# DataLogger_ver1.net
KiCad netlist of a schematic drawn in EAGLE
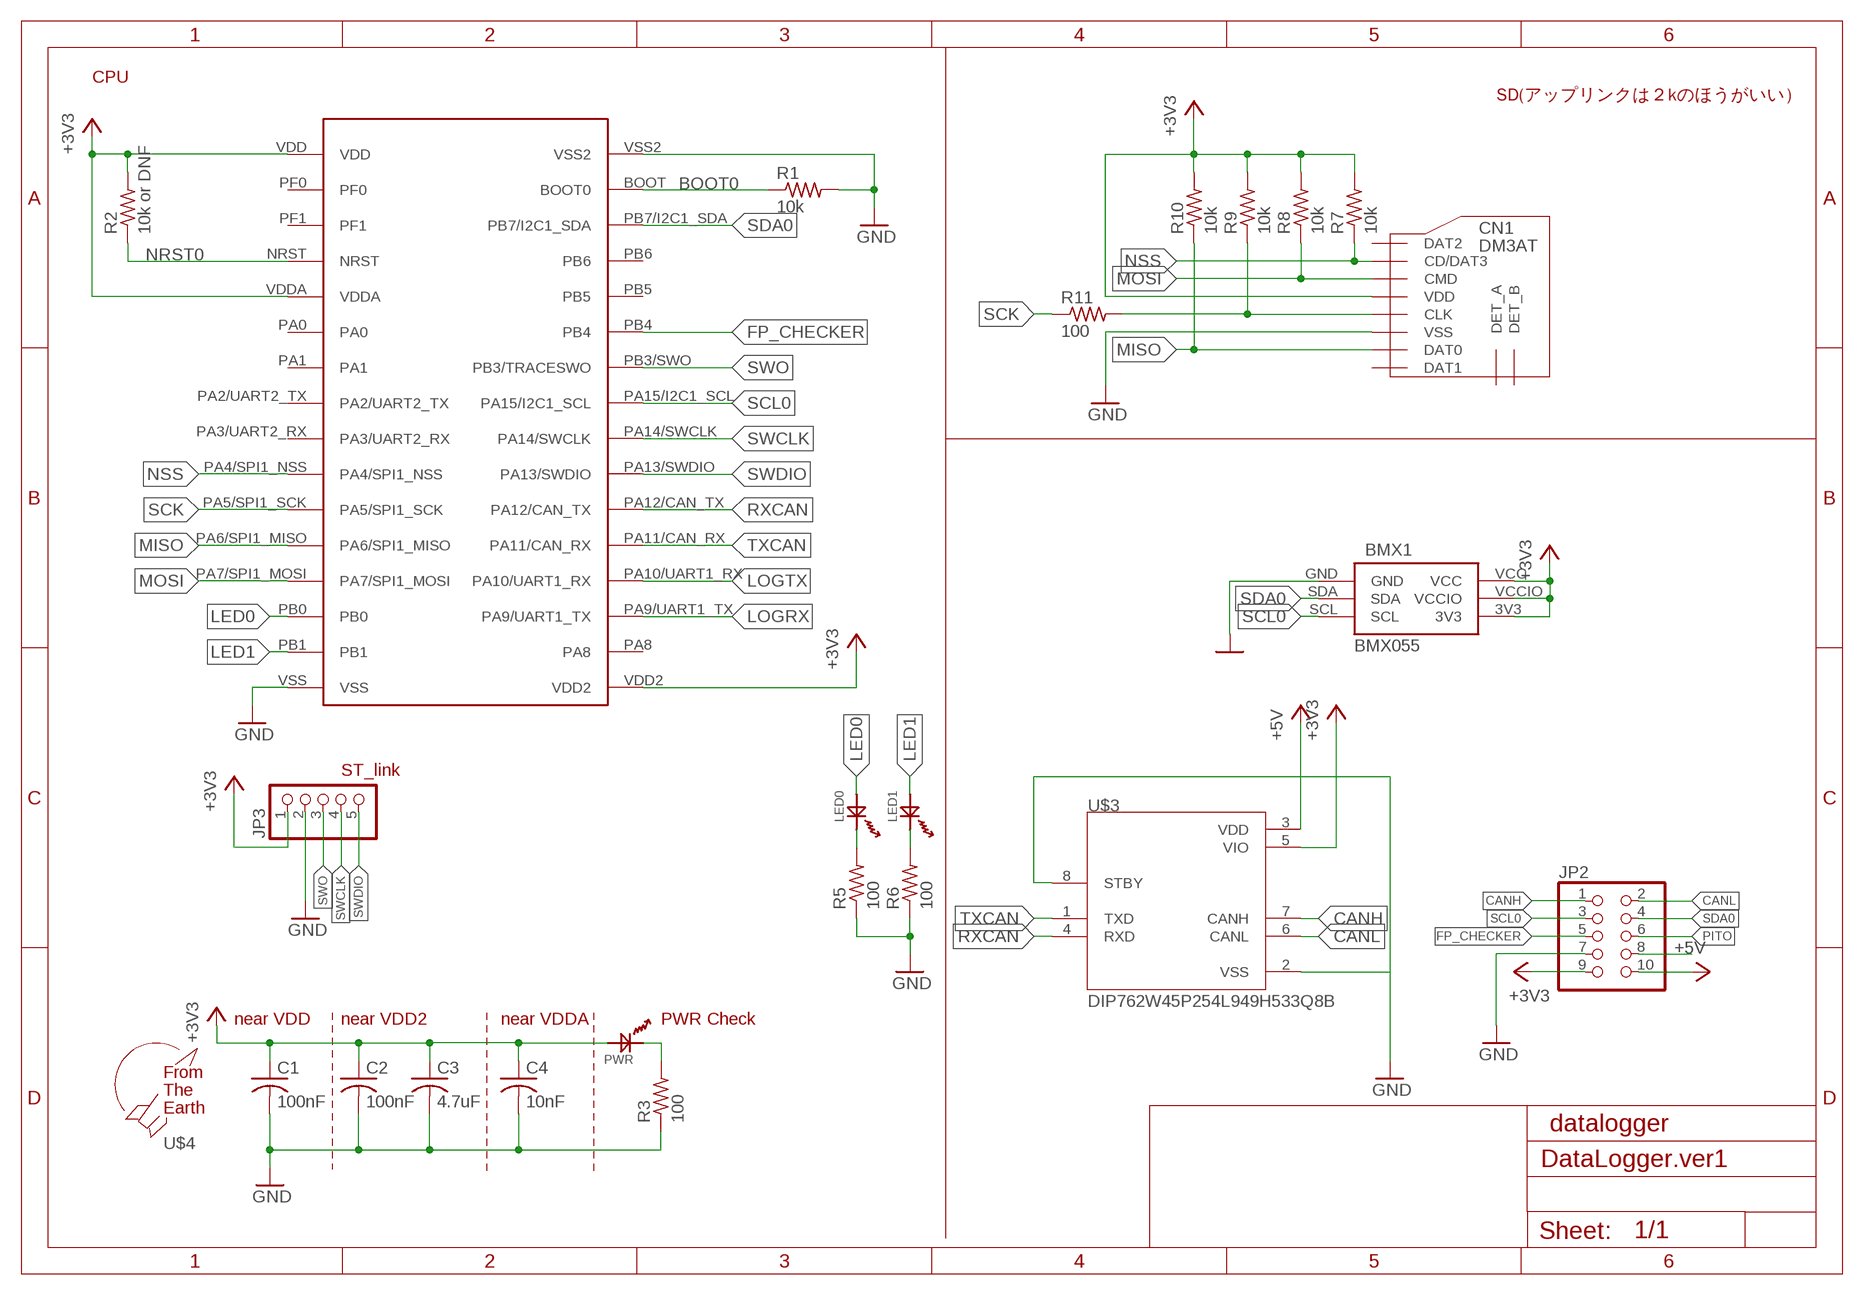
[diagram p0: schematic, sheet 1]

(export (version "E")
  (design (tool "Eeschema 10.0.6"))
  (components
    (comp (ref "BMX1")
      (value "BMX055")
      (footprint "eagle-import:BMX055")
      (libsource (lib "eagle-import") (part "BMX055"))
    )
    (comp (ref "C1")
      (value "100nF")
      (footprint "eagle-import:C1608")
      (libsource (lib "eagle-import") (part "C-USC1608"))
    )
    (comp (ref "C2")
      (value "100nF")
      (footprint "eagle-import:C1608")
      (libsource (lib "eagle-import") (part "C-USC1608"))
    )
    (comp (ref "C3")
      (value "4.7uF")
      (footprint "eagle-import:C1608")
      (libsource (lib "eagle-import") (part "C-USC1608"))
    )
    (comp (ref "C4")
      (value "10nF")
      (footprint "eagle-import:C1608")
      (libsource (lib "eagle-import") (part "C-USC1608"))
    )
    (comp (ref "CN1")
      (value "DM3AT")
      (footprint "eagle-import:DM3AT")
      (libsource (lib "eagle-import") (part "DM3AT"))
    )
    (comp (ref "JP2")
      (value "PINHD-2X5/90")
      (footprint "eagle-import:2X05_90")
      (libsource (lib "eagle-import") (part "PINHD-2X5/90"))
    )
    (comp (ref "JP3")
      (value "PINHD-1X5/90")
      (footprint "eagle-import:1X05_90")
      (libsource (lib "eagle-import") (part "PINHD-1X5/90"))
    )
    (comp (ref "LED0")
      (value "OSXX1608C1A")
      (footprint "eagle-import:OSXX1608C1A")
      (libsource (lib "eagle-import") (part "OSXX1608C1A"))
    )
    (comp (ref "LED1")
      (value "OSXX1608C1A")
      (footprint "eagle-import:OSXX1608C1A")
      (libsource (lib "eagle-import") (part "OSXX1608C1A"))
    )
    (comp (ref "PWR")
      (value "OSXX1608C1A")
      (footprint "eagle-import:OSXX1608C1A")
      (libsource (lib "eagle-import") (part "OSXX1608C1A"))
    )
    (comp (ref "R1")
      (value "10k")
      (footprint "eagle-import:R0603")
      (libsource (lib "eagle-import") (part "R-US_R0603"))
    )
    (comp (ref "R2")
      (value "10k or DNF")
      (footprint "eagle-import:R0603")
      (libsource (lib "eagle-import") (part "R-US_R0603"))
    )
    (comp (ref "R3")
      (value "100")
      (footprint "eagle-import:R0603")
      (libsource (lib "eagle-import") (part "R-US_R0603"))
    )
    (comp (ref "R5")
      (value "100")
      (footprint "eagle-import:R0603")
      (libsource (lib "eagle-import") (part "R-US_R0603"))
    )
    (comp (ref "R6")
      (value "100")
      (footprint "eagle-import:R0603")
      (libsource (lib "eagle-import") (part "R-US_R0603"))
    )
    (comp (ref "R7")
      (value "10k")
      (footprint "eagle-import:R0603")
      (libsource (lib "eagle-import") (part "R-US_R0603"))
    )
    (comp (ref "R8")
      (value "10k")
      (footprint "eagle-import:R0603")
      (libsource (lib "eagle-import") (part "R-US_R0603"))
    )
    (comp (ref "R9")
      (value "10k")
      (footprint "eagle-import:R0603")
      (libsource (lib "eagle-import") (part "R-US_R0603"))
    )
    (comp (ref "R10")
      (value "10k")
      (footprint "eagle-import:R0603")
      (libsource (lib "eagle-import") (part "R-US_R0603"))
    )
    (comp (ref "R11")
      (value "100")
      (footprint "eagle-import:R0603")
      (libsource (lib "eagle-import") (part "R-US_R0603"))
    )
    (comp (ref "STM0")
      (value "STM32F303K8")
      (footprint "eagle-import:STM32F303K8")
      (libsource (lib "eagle-import") (part "STM32F303K8"))
    )
    (comp (ref "U$3")
      (value "DIP762W45P254L949H533Q8B")
      (footprint "eagle-import:DIP762W45P254L949H533Q8B")
      (libsource (lib "eagle-import") (part "DIP762W45P254L949H533Q8B"))
    )
    (comp (ref "U$4")
      (value "F.T.E.LOGO")
      (footprint "eagle-import:LOGO")
      (libsource (lib "eagle-import") (part "F.T.E.LOGO"))
    )
  )
  (nets
    (net (code "1") (name "+3V3") (class "Default")
      (node (ref "BMX1") (pin "3V3") (pinfunction "3V3_3V3") (pintype "power_in"))
      (node (ref "BMX1") (pin "VCC") (pinfunction "VCC_VCC") (pintype "power_in"))
      (node (ref "BMX1") (pin "VCCIO") (pinfunction "VCCIO_VCCIO") (pintype "power_in"))
      (node (ref "C1") (pin "1") (pinfunction "1_1") (pintype "passive"))
      (node (ref "C2") (pin "1") (pinfunction "1_1") (pintype "passive"))
      (node (ref "C3") (pin "1") (pinfunction "1_1") (pintype "passive"))
      (node (ref "C4") (pin "1") (pinfunction "1_1") (pintype "passive"))
      (node (ref "CN1") (pin "VDD") (pinfunction "VDD_VDD") (pintype "bidirectional"))
      (node (ref "JP2") (pin "9") (pinfunction "9_9") (pintype "passive"))
      (node (ref "JP3") (pin "1") (pinfunction "1_1") (pintype "passive"))
      (node (ref "PWR") (pin "AN") (pinfunction "AN_AN") (pintype "bidirectional"))
      (node (ref "R10") (pin "2") (pinfunction "2_2") (pintype "passive"))
      (node (ref "R2") (pin "2") (pinfunction "2_2") (pintype "passive"))
      (node (ref "R7") (pin "2") (pinfunction "2_2") (pintype "passive"))
      (node (ref "R8") (pin "2") (pinfunction "2_2") (pintype "passive"))
      (node (ref "R9") (pin "2") (pinfunction "2_2") (pintype "passive"))
      (node (ref "STM0") (pin "VDD") (pinfunction "VDD_VDD") (pintype "power_in"))
      (node (ref "STM0") (pin "VDD2") (pinfunction "VDD2_VDD2") (pintype "power_in"))
      (node (ref "STM0") (pin "VDDA") (pinfunction "VDDA_VDDA") (pintype "power_in"))
      (node (ref "U$3") (pin "5") (pinfunction "VIO_5") (pintype "power_in"))
    )
    (net (code "2") (name "+5V") (class "Default")
      (node (ref "JP2") (pin "10") (pinfunction "10_10") (pintype "passive"))
      (node (ref "U$3") (pin "3") (pinfunction "VDD_3") (pintype "power_in"))
    )
    (net (code "3") (name "/BOOT0") (class "Default")
      (node (ref "R1") (pin "1") (pinfunction "1_1") (pintype "passive"))
      (node (ref "STM0") (pin "BOOT") (pinfunction "BOOT0_BOOT") (pintype "bidirectional"))
    )
    (net (code "4") (name "/NRST0") (class "Default")
      (node (ref "R2") (pin "1") (pinfunction "1_1") (pintype "passive"))
      (node (ref "STM0") (pin "NRST") (pinfunction "NRST_NRST") (pintype "bidirectional"))
    )
    (net (code "5") (name "CANH") (class "Default")
      (node (ref "JP2") (pin "1") (pinfunction "1_1") (pintype "passive"))
      (node (ref "U$3") (pin "7") (pinfunction "CANH_7") (pintype "bidirectional"))
    )
    (net (code "6") (name "CANL") (class "Default")
      (node (ref "JP2") (pin "2") (pinfunction "2_2") (pintype "passive"))
      (node (ref "U$3") (pin "6") (pinfunction "CANL_6") (pintype "bidirectional"))
    )
    (net (code "7") (name "FP_CHECKER") (class "Default")
      (node (ref "JP2") (pin "5") (pinfunction "5_5") (pintype "passive"))
      (node (ref "STM0") (pin "PB4") (pinfunction "PB4_PB4") (pintype "bidirectional"))
    )
    (net (code "8") (name "GND") (class "Default")
      (node (ref "BMX1") (pin "GND") (pinfunction "GND_GND") (pintype "power_in"))
      (node (ref "C1") (pin "2") (pinfunction "2_2") (pintype "passive"))
      (node (ref "C2") (pin "2") (pinfunction "2_2") (pintype "passive"))
      (node (ref "C3") (pin "2") (pinfunction "2_2") (pintype "passive"))
      (node (ref "C4") (pin "2") (pinfunction "2_2") (pintype "passive"))
      (node (ref "CN1") (pin "VSS") (pinfunction "VSS_VSS") (pintype "bidirectional"))
      (node (ref "JP2") (pin "7") (pinfunction "7_7") (pintype "passive"))
      (node (ref "JP3") (pin "2") (pinfunction "2_2") (pintype "passive"))
      (node (ref "R1") (pin "2") (pinfunction "2_2") (pintype "passive"))
      (node (ref "R3") (pin "1") (pinfunction "1_1") (pintype "passive"))
      (node (ref "R5") (pin "1") (pinfunction "1_1") (pintype "passive"))
      (node (ref "R6") (pin "1") (pinfunction "1_1") (pintype "passive"))
      (node (ref "STM0") (pin "VSS") (pinfunction "VSS_VSS") (pintype "power_in"))
      (node (ref "STM0") (pin "VSS2") (pinfunction "VSS2_VSS2") (pintype "power_in"))
      (node (ref "U$3") (pin "2") (pinfunction "VSS_2") (pintype "power_in"))
      (node (ref "U$3") (pin "8") (pinfunction "STBY_8") (pintype "input"))
    )
    (net (code "9") (name "LED0") (class "Default")
      (node (ref "LED0") (pin "AN") (pinfunction "AN_AN") (pintype "bidirectional"))
      (node (ref "STM0") (pin "PB0") (pinfunction "PB0_PB0") (pintype "bidirectional"))
    )
    (net (code "10") (name "LED1") (class "Default")
      (node (ref "LED1") (pin "AN") (pinfunction "AN_AN") (pintype "bidirectional"))
      (node (ref "STM0") (pin "PB1") (pinfunction "PB1_PB1") (pintype "bidirectional"))
    )
    (net (code "11") (name "LOGRX") (class "Default")
      (node (ref "STM0") (pin "PA9/UART1_TX") (pinfunction "PA9/UART1_TX_PA9/UART1_TX") (pintype "bidirectional"))
    )
    (net (code "12") (name "LOGTX") (class "Default")
      (node (ref "STM0") (pin "PA10/UART1_RX") (pinfunction "PA10/UART1_RX_PA10/UART1_RX") (pintype "bidirectional"))
    )
    (net (code "13") (name "MISO") (class "Default")
      (node (ref "CN1") (pin "DAT0") (pinfunction "DAT0_DAT0") (pintype "bidirectional"))
      (node (ref "R10") (pin "1") (pinfunction "1_1") (pintype "passive"))
      (node (ref "STM0") (pin "PA6/SPI1_MISO") (pinfunction "PA6/SPI1_MISO_PA6/SPI1_MISO") (pintype "bidirectional"))
    )
    (net (code "14") (name "MOSI") (class "Default")
      (node (ref "CN1") (pin "CMD") (pinfunction "CMD_CMD") (pintype "bidirectional"))
      (node (ref "R8") (pin "1") (pinfunction "1_1") (pintype "passive"))
      (node (ref "STM0") (pin "PA7/SPI1_MOSI") (pinfunction "PA7/SPI1_MOSI_PA7/SPI1_MOSI") (pintype "bidirectional"))
    )
    (net (code "15") (name "NSS") (class "Default")
      (node (ref "CN1") (pin "CD/DAT3") (pinfunction "CD/DAT3_CD/DAT3") (pintype "bidirectional"))
      (node (ref "R7") (pin "1") (pinfunction "1_1") (pintype "passive"))
      (node (ref "STM0") (pin "PA4/SPI1_NSS") (pinfunction "PA4/SPI1_NSS_PA4/SPI1_NSS") (pintype "bidirectional"))
    )
    (net (code "16") (name "Net-(CN1-PadCLK)") (class "Default")
      (node (ref "CN1") (pin "CLK") (pinfunction "CLK_CLK") (pintype "bidirectional"))
      (node (ref "R11") (pin "2") (pinfunction "2_2") (pintype "passive"))
      (node (ref "R9") (pin "1") (pinfunction "1_1") (pintype "passive"))
    )
    (net (code "17") (name "Net-(LED0-PadCT)") (class "Default")
      (node (ref "LED0") (pin "CT") (pinfunction "CT_CT") (pintype "bidirectional"))
      (node (ref "R5") (pin "2") (pinfunction "2_2") (pintype "passive"))
    )
    (net (code "18") (name "Net-(LED1-PadCT)") (class "Default")
      (node (ref "LED1") (pin "CT") (pinfunction "CT_CT") (pintype "bidirectional"))
      (node (ref "R6") (pin "2") (pinfunction "2_2") (pintype "passive"))
    )
    (net (code "19") (name "Net-(PWR-PadCT)") (class "Default")
      (node (ref "PWR") (pin "CT") (pinfunction "CT_CT") (pintype "bidirectional"))
      (node (ref "R3") (pin "2") (pinfunction "2_2") (pintype "passive"))
    )
    (net (code "20") (name "PITO") (class "Default")
      (node (ref "JP2") (pin "6") (pinfunction "6_6") (pintype "passive"))
    )
    (net (code "21") (name "RXCAN") (class "Default")
      (node (ref "STM0") (pin "PA12/CAN_TX") (pinfunction "PA12/CAN_TX_PA12/CAN_TX") (pintype "bidirectional"))
      (node (ref "U$3") (pin "4") (pinfunction "RXD_4") (pintype "output"))
    )
    (net (code "22") (name "SCK") (class "Default")
      (node (ref "R11") (pin "1") (pinfunction "1_1") (pintype "passive"))
      (node (ref "STM0") (pin "PA5/SPI1_SCK") (pinfunction "PA5/SPI1_SCK_PA5/SPI1_SCK") (pintype "bidirectional"))
    )
    (net (code "23") (name "SCL0") (class "Default")
      (node (ref "BMX1") (pin "SCL") (pinfunction "SCL_SCL") (pintype "bidirectional"))
      (node (ref "JP2") (pin "3") (pinfunction "3_3") (pintype "passive"))
      (node (ref "STM0") (pin "PA15/I2C1_SCL") (pinfunction "PA15/I2C1_SCL_PA15/I2C1_SCL") (pintype "bidirectional"))
    )
    (net (code "24") (name "SDA0") (class "Default")
      (node (ref "BMX1") (pin "SDA") (pinfunction "SDA_SDA") (pintype "bidirectional"))
      (node (ref "JP2") (pin "4") (pinfunction "4_4") (pintype "passive"))
      (node (ref "STM0") (pin "PB7/I2C1_SDA") (pinfunction "PB7/I2C1_SDA_PB7/I2C1_SDA") (pintype "bidirectional"))
    )
    (net (code "25") (name "SWCLK") (class "Default")
      (node (ref "JP3") (pin "4") (pinfunction "4_4") (pintype "passive"))
      (node (ref "STM0") (pin "PA14/SWCLK") (pinfunction "PA14/SWCLK_PA14/SWCLK") (pintype "bidirectional"))
    )
    (net (code "26") (name "SWDIO") (class "Default")
      (node (ref "JP3") (pin "5") (pinfunction "5_5") (pintype "passive"))
      (node (ref "STM0") (pin "PA13/SWDIO") (pinfunction "PA13/SWDIO_PA13/SWDIO") (pintype "bidirectional"))
    )
    (net (code "27") (name "SWO") (class "Default")
      (node (ref "JP3") (pin "3") (pinfunction "3_3") (pintype "passive"))
      (node (ref "STM0") (pin "PB3/SWO") (pinfunction "PB3/TRACESWO_PB3/SWO") (pintype "bidirectional"))
    )
    (net (code "28") (name "TXCAN") (class "Default")
      (node (ref "STM0") (pin "PA11/CAN_RX") (pinfunction "PA11/CAN_RX_PA11/CAN_RX") (pintype "bidirectional"))
      (node (ref "U$3") (pin "1") (pinfunction "TXD_1") (pintype "input"))
    )
    (net (code "29") (name "unconnected-(CN1-PadDAT1)") (class "Default")
      (node (ref "CN1") (pin "DAT1") (pinfunction "DAT1_DAT1") (pintype "bidirectional"))
    )
    (net (code "30") (name "unconnected-(CN1-PadDAT2)") (class "Default")
      (node (ref "CN1") (pin "DAT2") (pinfunction "DAT2_DAT2") (pintype "bidirectional"))
    )
    (net (code "31") (name "unconnected-(CN1-PadDET_A)") (class "Default")
      (node (ref "CN1") (pin "DET_A") (pinfunction "DET_A_DET_A") (pintype "bidirectional"))
    )
    (net (code "32") (name "unconnected-(CN1-PadDET_B)") (class "Default")
      (node (ref "CN1") (pin "DET_B") (pinfunction "DET_B_DET_B") (pintype "bidirectional"))
    )
    (net (code "33") (name "unconnected-(JP2-Pad8)") (class "Default")
      (node (ref "JP2") (pin "8") (pinfunction "8_8") (pintype "passive"))
    )
    (net (code "34") (name "unconnected-(STM0-PadPA0)") (class "Default")
      (node (ref "STM0") (pin "PA0") (pinfunction "PA0_PA0") (pintype "bidirectional"))
    )
    (net (code "35") (name "unconnected-(STM0-PadPA1)") (class "Default")
      (node (ref "STM0") (pin "PA1") (pinfunction "PA1_PA1") (pintype "bidirectional"))
    )
    (net (code "36") (name "unconnected-(STM0-PadPA2{slash}UART2_TX)") (class "Default")
      (node (ref "STM0") (pin "PA2/UART2_TX") (pinfunction "PA2/UART2_TX_PA2/UART2_TX") (pintype "bidirectional"))
    )
    (net (code "37") (name "unconnected-(STM0-PadPA3{slash}UART2_RX)") (class "Default")
      (node (ref "STM0") (pin "PA3/UART2_RX") (pinfunction "PA3/UART2_RX_PA3/UART2_RX") (pintype "bidirectional"))
    )
    (net (code "38") (name "unconnected-(STM0-PadPA8)") (class "Default")
      (node (ref "STM0") (pin "PA8") (pinfunction "PA8_PA8") (pintype "bidirectional"))
    )
    (net (code "39") (name "unconnected-(STM0-PadPB5)") (class "Default")
      (node (ref "STM0") (pin "PB5") (pinfunction "PB5_PB5") (pintype "bidirectional"))
    )
    (net (code "40") (name "unconnected-(STM0-PadPB6)") (class "Default")
      (node (ref "STM0") (pin "PB6") (pinfunction "PB6_PB6") (pintype "bidirectional"))
    )
    (net (code "41") (name "unconnected-(STM0-PadPF0)") (class "Default")
      (node (ref "STM0") (pin "PF0") (pinfunction "PF0_PF0") (pintype "bidirectional"))
    )
    (net (code "42") (name "unconnected-(STM0-PadPF1)") (class "Default")
      (node (ref "STM0") (pin "PF1") (pinfunction "PF1_PF1") (pintype "bidirectional"))
    )
  )
)
